# BackplaneConnector.net
KiCad netlist of a schematic drawn in Altium Designer
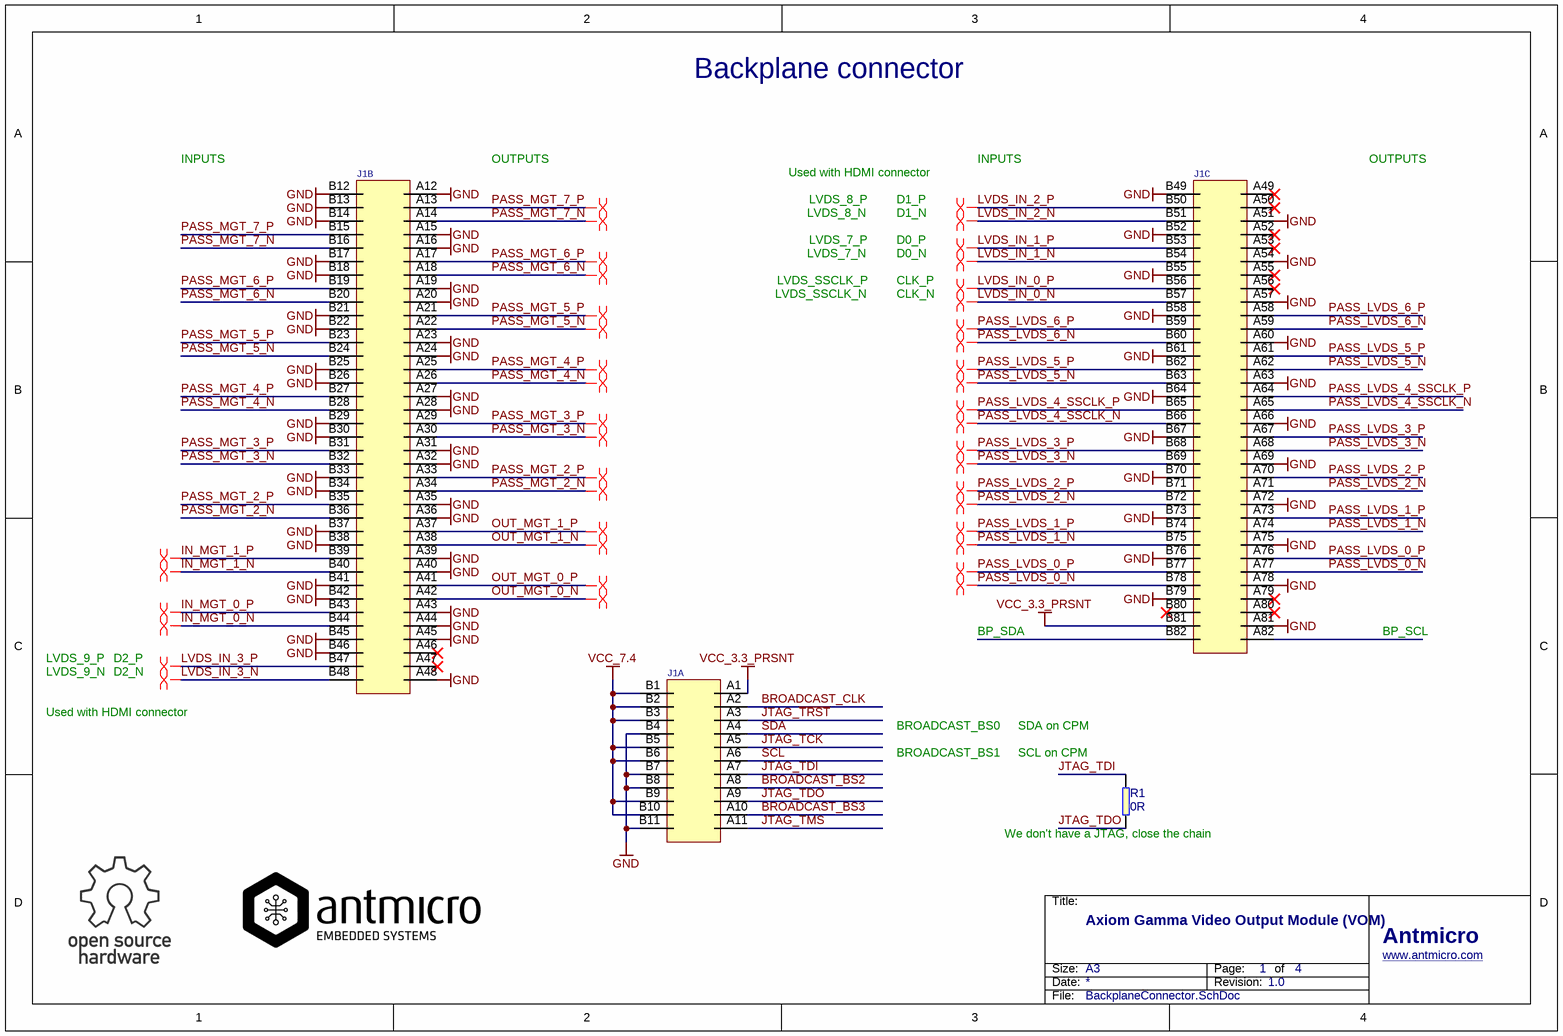
[diagram p0: BackplaneConnector.SchDoc]

(export (version "E")
  (design (tool "Eeschema 10.0.6"))
  (components
    (comp (ref "J1")
      (value "~")
      (footprint "PCIEX16")
      (description "PCB Only")
      (fields (field (name "PART NUMBER") "PCIEX16") (field (name "MANUFACTURER") "PCB ONLY"))
      (libsource (lib "VOM") (part "PCIEX16"))
    )
    (comp (ref "R1")
      (value "0R")
      (footprint "0402")
      (description "SMT Resistor 0402")
      (fields (field (name "PART NUMBER") "R_0R_0402") (field (name "MANUFACTURER") "MULTICOMP"))
      (libsource (lib "VOM") (part "R_0R_0402"))
    )
  )
  (nets
    (net (code "1") (name "/BROADCAST_BS2") (class "Default")
      (node (ref "J1") (pin "A8") (pinfunction "A8_A8") (pintype "passive"))
    )
    (net (code "2") (name "/BROADCAST_BS3") (class "Default")
      (node (ref "J1") (pin "A10") (pinfunction "A10_A10") (pintype "passive"))
    )
    (net (code "3") (name "/BROADCAST_CLK") (class "Default")
      (node (ref "J1") (pin "A2") (pinfunction "A2_A2") (pintype "passive"))
    )
    (net (code "4") (name "/IN_MGT_0_N") (class "Default")
      (node (ref "J1") (pin "B44") (pinfunction "B44_B44") (pintype "passive"))
    )
    (net (code "5") (name "/IN_MGT_0_P") (class "Default")
      (node (ref "J1") (pin "B43") (pinfunction "B43_B43") (pintype "passive"))
    )
    (net (code "6") (name "/IN_MGT_1_N") (class "Default")
      (node (ref "J1") (pin "B40") (pinfunction "B40_B40") (pintype "passive"))
    )
    (net (code "7") (name "/IN_MGT_1_P") (class "Default")
      (node (ref "J1") (pin "B39") (pinfunction "B39_B39") (pintype "passive"))
    )
    (net (code "8") (name "/JTAG_TCK") (class "Default")
      (node (ref "J1") (pin "A5") (pinfunction "A5_A5") (pintype "passive"))
    )
    (net (code "9") (name "/JTAG_TDI") (class "Default")
      (node (ref "J1") (pin "A7") (pinfunction "A7_A7") (pintype "passive"))
      (node (ref "R1") (pin "2") (pintype "passive"))
    )
    (net (code "10") (name "/JTAG_TDO") (class "Default")
      (node (ref "J1") (pin "A9") (pinfunction "A9_A9") (pintype "passive"))
      (node (ref "R1") (pin "1") (pintype "passive"))
    )
    (net (code "11") (name "/JTAG_TMS") (class "Default")
      (node (ref "J1") (pin "A11") (pinfunction "A11_A11") (pintype "passive"))
    )
    (net (code "12") (name "/JTAG_~{TRST}") (class "Default")
      (node (ref "J1") (pin "A3") (pinfunction "A3_A3") (pintype "passive"))
    )
    (net (code "13") (name "/LVDS_IN_0_N") (class "Default")
      (node (ref "J1") (pin "B57") (pinfunction "B57_B57") (pintype "passive"))
    )
    (net (code "14") (name "/LVDS_IN_0_P") (class "Default")
      (node (ref "J1") (pin "B56") (pinfunction "B56_B56") (pintype "passive"))
    )
    (net (code "15") (name "/LVDS_IN_1_N") (class "Default")
      (node (ref "J1") (pin "B54") (pinfunction "B54_B54") (pintype "passive"))
    )
    (net (code "16") (name "/LVDS_IN_1_P") (class "Default")
      (node (ref "J1") (pin "B53") (pinfunction "B53_B53") (pintype "passive"))
    )
    (net (code "17") (name "/LVDS_IN_2_N") (class "Default")
      (node (ref "J1") (pin "B51") (pinfunction "B51_B51") (pintype "passive"))
    )
    (net (code "18") (name "/LVDS_IN_2_P") (class "Default")
      (node (ref "J1") (pin "B50") (pinfunction "B50_B50") (pintype "passive"))
    )
    (net (code "19") (name "/LVDS_IN_3_N") (class "Default")
      (node (ref "J1") (pin "B48") (pinfunction "B48_B48") (pintype "passive"))
    )
    (net (code "20") (name "/LVDS_IN_3_P") (class "Default")
      (node (ref "J1") (pin "B47") (pinfunction "B47_B47") (pintype "passive"))
    )
    (net (code "21") (name "/OUT_MGT_0_N") (class "Default")
      (node (ref "J1") (pin "A42") (pinfunction "A42_A42") (pintype "passive"))
    )
    (net (code "22") (name "/OUT_MGT_0_P") (class "Default")
      (node (ref "J1") (pin "A41") (pinfunction "A41_A41") (pintype "passive"))
    )
    (net (code "23") (name "/OUT_MGT_1_N") (class "Default")
      (node (ref "J1") (pin "A38") (pinfunction "A38_A38") (pintype "passive"))
    )
    (net (code "24") (name "/OUT_MGT_1_P") (class "Default")
      (node (ref "J1") (pin "A37") (pinfunction "A37_A37") (pintype "passive"))
    )
    (net (code "25") (name "/PASS_LVDS_0_N") (class "Default")
      (node (ref "J1") (pin "A77") (pinfunction "A77_A77") (pintype "passive"))
      (node (ref "J1") (pin "B78") (pinfunction "B78_B78") (pintype "passive"))
    )
    (net (code "26") (name "/PASS_LVDS_0_P") (class "Default")
      (node (ref "J1") (pin "A76") (pinfunction "A76_A76") (pintype "passive"))
      (node (ref "J1") (pin "B77") (pinfunction "B77_B77") (pintype "passive"))
    )
    (net (code "27") (name "/PASS_LVDS_1_N") (class "Default")
      (node (ref "J1") (pin "A74") (pinfunction "A74_A74") (pintype "passive"))
      (node (ref "J1") (pin "B75") (pinfunction "B75_B75") (pintype "passive"))
    )
    (net (code "28") (name "/PASS_LVDS_1_P") (class "Default")
      (node (ref "J1") (pin "A73") (pinfunction "A73_A73") (pintype "passive"))
      (node (ref "J1") (pin "B74") (pinfunction "B74_B74") (pintype "passive"))
    )
    (net (code "29") (name "/PASS_LVDS_2_N") (class "Default")
      (node (ref "J1") (pin "A71") (pinfunction "A71_A71") (pintype "passive"))
      (node (ref "J1") (pin "B72") (pinfunction "B72_B72") (pintype "passive"))
    )
    (net (code "30") (name "/PASS_LVDS_2_P") (class "Default")
      (node (ref "J1") (pin "A70") (pinfunction "A70_A70") (pintype "passive"))
      (node (ref "J1") (pin "B71") (pinfunction "B71_B71") (pintype "passive"))
    )
    (net (code "31") (name "/PASS_LVDS_3_N") (class "Default")
      (node (ref "J1") (pin "A68") (pinfunction "A68_A68") (pintype "passive"))
      (node (ref "J1") (pin "B69") (pinfunction "B69_B69") (pintype "passive"))
    )
    (net (code "32") (name "/PASS_LVDS_3_P") (class "Default")
      (node (ref "J1") (pin "A67") (pinfunction "A67_A67") (pintype "passive"))
      (node (ref "J1") (pin "B68") (pinfunction "B68_B68") (pintype "passive"))
    )
    (net (code "33") (name "/PASS_LVDS_4_SSCLK_N") (class "Default")
      (node (ref "J1") (pin "A65") (pinfunction "A65_A65") (pintype "passive"))
      (node (ref "J1") (pin "B66") (pinfunction "B66_B66") (pintype "passive"))
    )
    (net (code "34") (name "/PASS_LVDS_4_SSCLK_P") (class "Default")
      (node (ref "J1") (pin "A64") (pinfunction "A64_A64") (pintype "passive"))
      (node (ref "J1") (pin "B65") (pinfunction "B65_B65") (pintype "passive"))
    )
    (net (code "35") (name "/PASS_LVDS_5_N") (class "Default")
      (node (ref "J1") (pin "A62") (pinfunction "A62_A62") (pintype "passive"))
      (node (ref "J1") (pin "B63") (pinfunction "B63_B63") (pintype "passive"))
    )
    (net (code "36") (name "/PASS_LVDS_5_P") (class "Default")
      (node (ref "J1") (pin "A61") (pinfunction "A61_A61") (pintype "passive"))
      (node (ref "J1") (pin "B62") (pinfunction "B62_B62") (pintype "passive"))
    )
    (net (code "37") (name "/PASS_LVDS_6_N") (class "Default")
      (node (ref "J1") (pin "A59") (pinfunction "A59_A59") (pintype "passive"))
      (node (ref "J1") (pin "B60") (pinfunction "B60_B60") (pintype "passive"))
    )
    (net (code "38") (name "/PASS_LVDS_6_P") (class "Default")
      (node (ref "J1") (pin "A58") (pinfunction "A58_A58") (pintype "passive"))
      (node (ref "J1") (pin "B59") (pinfunction "B59_B59") (pintype "passive"))
    )
    (net (code "39") (name "/PASS_MGT_2_N") (class "Default")
      (node (ref "J1") (pin "A34") (pinfunction "A34_A34") (pintype "passive"))
      (node (ref "J1") (pin "B36") (pinfunction "B36_B36") (pintype "passive"))
    )
    (net (code "40") (name "/PASS_MGT_2_P") (class "Default")
      (node (ref "J1") (pin "A33") (pinfunction "A33_A33") (pintype "passive"))
      (node (ref "J1") (pin "B35") (pinfunction "B35_B35") (pintype "passive"))
    )
    (net (code "41") (name "/PASS_MGT_3_N") (class "Default")
      (node (ref "J1") (pin "A30") (pinfunction "A30_A30") (pintype "passive"))
      (node (ref "J1") (pin "B32") (pinfunction "B32_B32") (pintype "passive"))
    )
    (net (code "42") (name "/PASS_MGT_3_P") (class "Default")
      (node (ref "J1") (pin "A29") (pinfunction "A29_A29") (pintype "passive"))
      (node (ref "J1") (pin "B31") (pinfunction "B31_B31") (pintype "passive"))
    )
    (net (code "43") (name "/PASS_MGT_4_N") (class "Default")
      (node (ref "J1") (pin "A26") (pinfunction "A26_A26") (pintype "passive"))
      (node (ref "J1") (pin "B28") (pinfunction "B28_B28") (pintype "passive"))
    )
    (net (code "44") (name "/PASS_MGT_4_P") (class "Default")
      (node (ref "J1") (pin "A25") (pinfunction "A25_A25") (pintype "passive"))
      (node (ref "J1") (pin "B27") (pinfunction "B27_B27") (pintype "passive"))
    )
    (net (code "45") (name "/PASS_MGT_5_N") (class "Default")
      (node (ref "J1") (pin "A22") (pinfunction "A22_A22") (pintype "passive"))
      (node (ref "J1") (pin "B24") (pinfunction "B24_B24") (pintype "passive"))
    )
    (net (code "46") (name "/PASS_MGT_5_P") (class "Default")
      (node (ref "J1") (pin "A21") (pinfunction "A21_A21") (pintype "passive"))
      (node (ref "J1") (pin "B23") (pinfunction "B23_B23") (pintype "passive"))
    )
    (net (code "47") (name "/PASS_MGT_6_N") (class "Default")
      (node (ref "J1") (pin "A18") (pinfunction "A18_A18") (pintype "passive"))
      (node (ref "J1") (pin "B20") (pinfunction "B20_B20") (pintype "passive"))
    )
    (net (code "48") (name "/PASS_MGT_6_P") (class "Default")
      (node (ref "J1") (pin "A17") (pinfunction "A17_A17") (pintype "passive"))
      (node (ref "J1") (pin "B19") (pinfunction "B19_B19") (pintype "passive"))
    )
    (net (code "49") (name "/PASS_MGT_7_N") (class "Default")
      (node (ref "J1") (pin "A14") (pinfunction "A14_A14") (pintype "passive"))
      (node (ref "J1") (pin "B16") (pinfunction "B16_B16") (pintype "passive"))
    )
    (net (code "50") (name "/PASS_MGT_7_P") (class "Default")
      (node (ref "J1") (pin "A13") (pinfunction "A13_A13") (pintype "passive"))
      (node (ref "J1") (pin "B15") (pinfunction "B15_B15") (pintype "passive"))
    )
    (net (code "51") (name "/SCL") (class "Default")
      (node (ref "J1") (pin "A6") (pinfunction "A6_A6") (pintype "passive"))
    )
    (net (code "52") (name "/SDA") (class "Default")
      (node (ref "J1") (pin "A4") (pinfunction "A4_A4") (pintype "passive"))
    )
    (net (code "53") (name "GND") (class "Default")
      (node (ref "J1") (pin "A12") (pinfunction "A12_A12") (pintype "passive"))
      (node (ref "J1") (pin "A15") (pinfunction "A15_A15") (pintype "passive"))
      (node (ref "J1") (pin "A16") (pinfunction "A16_A16") (pintype "passive"))
      (node (ref "J1") (pin "A19") (pinfunction "A19_A19") (pintype "passive"))
      (node (ref "J1") (pin "A20") (pinfunction "A20_A20") (pintype "passive"))
      (node (ref "J1") (pin "A23") (pinfunction "A23_A23") (pintype "passive"))
      (node (ref "J1") (pin "A24") (pinfunction "A24_A24") (pintype "passive"))
      (node (ref "J1") (pin "A27") (pinfunction "A27_A27") (pintype "passive"))
      (node (ref "J1") (pin "A28") (pinfunction "A28_A28") (pintype "passive"))
      (node (ref "J1") (pin "A31") (pinfunction "A31_A31") (pintype "passive"))
      (node (ref "J1") (pin "A32") (pinfunction "A32_A32") (pintype "passive"))
      (node (ref "J1") (pin "A35") (pinfunction "A35_A35") (pintype "passive"))
      (node (ref "J1") (pin "A36") (pinfunction "A36_A36") (pintype "passive"))
      (node (ref "J1") (pin "A39") (pinfunction "A39_A39") (pintype "passive"))
      (node (ref "J1") (pin "A40") (pinfunction "A40_A40") (pintype "passive"))
      (node (ref "J1") (pin "A43") (pinfunction "A43_A43") (pintype "passive"))
      (node (ref "J1") (pin "A44") (pinfunction "A44_A44") (pintype "passive"))
      (node (ref "J1") (pin "A45") (pinfunction "A45_A45") (pintype "passive"))
      (node (ref "J1") (pin "A48") (pinfunction "A48_A48") (pintype "passive"))
      (node (ref "J1") (pin "A51") (pinfunction "A51_A51") (pintype "passive"))
      (node (ref "J1") (pin "A54") (pinfunction "A54_A54") (pintype "passive"))
      (node (ref "J1") (pin "A57") (pinfunction "A57_A57") (pintype "passive"))
      (node (ref "J1") (pin "A60") (pinfunction "A60_A60") (pintype "passive"))
      (node (ref "J1") (pin "A63") (pinfunction "A63_A63") (pintype "passive"))
      (node (ref "J1") (pin "A66") (pinfunction "A66_A66") (pintype "passive"))
      (node (ref "J1") (pin "A69") (pinfunction "A69_A69") (pintype "passive"))
      (node (ref "J1") (pin "A72") (pinfunction "A72_A72") (pintype "passive"))
      (node (ref "J1") (pin "A75") (pinfunction "A75_A75") (pintype "passive"))
      (node (ref "J1") (pin "A78") (pinfunction "A78_A78") (pintype "passive"))
      (node (ref "J1") (pin "A81") (pinfunction "A81_A81") (pintype "passive"))
      (node (ref "J1") (pin "B11") (pinfunction "B11_B11") (pintype "passive"))
      (node (ref "J1") (pin "B12") (pinfunction "B12_B12") (pintype "passive"))
      (node (ref "J1") (pin "B13") (pinfunction "B13_B13") (pintype "passive"))
      (node (ref "J1") (pin "B14") (pinfunction "B14_B14") (pintype "passive"))
      (node (ref "J1") (pin "B17") (pinfunction "B17_B17") (pintype "passive"))
      (node (ref "J1") (pin "B18") (pinfunction "B18_B18") (pintype "passive"))
      (node (ref "J1") (pin "B21") (pinfunction "B21_B21") (pintype "passive"))
      (node (ref "J1") (pin "B22") (pinfunction "B22_B22") (pintype "passive"))
      (node (ref "J1") (pin "B25") (pinfunction "B25_B25") (pintype "passive"))
      (node (ref "J1") (pin "B26") (pinfunction "B26_B26") (pintype "passive"))
      (node (ref "J1") (pin "B29") (pinfunction "B29_B29") (pintype "passive"))
      (node (ref "J1") (pin "B30") (pinfunction "B30_B30") (pintype "passive"))
      (node (ref "J1") (pin "B33") (pinfunction "B33_B33") (pintype "passive"))
      (node (ref "J1") (pin "B34") (pinfunction "B34_B34") (pintype "passive"))
      (node (ref "J1") (pin "B37") (pinfunction "B37_B37") (pintype "passive"))
      (node (ref "J1") (pin "B38") (pinfunction "B38_B38") (pintype "passive"))
      (node (ref "J1") (pin "B4") (pinfunction "B4_B4") (pintype "passive"))
      (node (ref "J1") (pin "B41") (pinfunction "B41_B41") (pintype "passive"))
      (node (ref "J1") (pin "B42") (pinfunction "B42_B42") (pintype "passive"))
      (node (ref "J1") (pin "B45") (pinfunction "B45_B45") (pintype "passive"))
      (node (ref "J1") (pin "B46") (pinfunction "B46_B46") (pintype "passive"))
      (node (ref "J1") (pin "B49") (pinfunction "B49_B49") (pintype "passive"))
      (node (ref "J1") (pin "B52") (pinfunction "B52_B52") (pintype "passive"))
      (node (ref "J1") (pin "B55") (pinfunction "B55_B55") (pintype "passive"))
      (node (ref "J1") (pin "B58") (pinfunction "B58_B58") (pintype "passive"))
      (node (ref "J1") (pin "B61") (pinfunction "B61_B61") (pintype "passive"))
      (node (ref "J1") (pin "B64") (pinfunction "B64_B64") (pintype "passive"))
      (node (ref "J1") (pin "B67") (pinfunction "B67_B67") (pintype "passive"))
      (node (ref "J1") (pin "B7") (pinfunction "B7_B7") (pintype "passive"))
      (node (ref "J1") (pin "B70") (pinfunction "B70_B70") (pintype "passive"))
      (node (ref "J1") (pin "B73") (pinfunction "B73_B73") (pintype "passive"))
      (node (ref "J1") (pin "B76") (pinfunction "B76_B76") (pintype "passive"))
      (node (ref "J1") (pin "B79") (pinfunction "B79_B79") (pintype "passive"))
      (node (ref "J1") (pin "B8") (pinfunction "B8_B8") (pintype "passive"))
    )
    (net (code "54") (name "VCC_3.3_PRSNT") (class "Default")
      (node (ref "J1") (pin "A1") (pinfunction "A1_A1") (pintype "passive"))
      (node (ref "J1") (pin "B81") (pinfunction "B81_B81") (pintype "passive"))
    )
    (net (code "55") (name "VCC_7.4") (class "Default")
      (node (ref "J1") (pin "B1") (pinfunction "B1_B1") (pintype "passive"))
      (node (ref "J1") (pin "B10") (pinfunction "B10_B10") (pintype "passive"))
      (node (ref "J1") (pin "B2") (pinfunction "B2_B2") (pintype "passive"))
      (node (ref "J1") (pin "B3") (pinfunction "B3_B3") (pintype "passive"))
      (node (ref "J1") (pin "B5") (pinfunction "B5_B5") (pintype "passive"))
      (node (ref "J1") (pin "B6") (pinfunction "B6_B6") (pintype "passive"))
      (node (ref "J1") (pin "B9") (pinfunction "B9_B9") (pintype "passive"))
    )
    (net (code "56") (name "unconnected-(J1-PadA46)") (class "Default")
      (node (ref "J1") (pin "A46") (pinfunction "A46_A46") (pintype "passive+no_connect"))
    )
    (net (code "57") (name "unconnected-(J1-PadA47)") (class "Default")
      (node (ref "J1") (pin "A47") (pinfunction "A47_A47") (pintype "passive+no_connect"))
    )
    (net (code "58") (name "unconnected-(J1-PadA49)") (class "Default")
      (node (ref "J1") (pin "A49") (pinfunction "A49_A49") (pintype "passive+no_connect"))
    )
    (net (code "59") (name "unconnected-(J1-PadA50)") (class "Default")
      (node (ref "J1") (pin "A50") (pinfunction "A50_A50") (pintype "passive+no_connect"))
    )
    (net (code "60") (name "unconnected-(J1-PadA52)") (class "Default")
      (node (ref "J1") (pin "A52") (pinfunction "A52_A52") (pintype "passive+no_connect"))
    )
    (net (code "61") (name "unconnected-(J1-PadA53)") (class "Default")
      (node (ref "J1") (pin "A53") (pinfunction "A53_A53") (pintype "passive+no_connect"))
    )
    (net (code "62") (name "unconnected-(J1-PadA55)") (class "Default")
      (node (ref "J1") (pin "A55") (pinfunction "A55_A55") (pintype "passive+no_connect"))
    )
    (net (code "63") (name "unconnected-(J1-PadA56)") (class "Default")
      (node (ref "J1") (pin "A56") (pinfunction "A56_A56") (pintype "passive+no_connect"))
    )
    (net (code "64") (name "unconnected-(J1-PadA79)") (class "Default")
      (node (ref "J1") (pin "A79") (pinfunction "A79_A79") (pintype "passive+no_connect"))
    )
    (net (code "65") (name "unconnected-(J1-PadA80)") (class "Default")
      (node (ref "J1") (pin "A80") (pinfunction "A80_A80") (pintype "passive+no_connect"))
    )
    (net (code "66") (name "unconnected-(J1-PadA82)") (class "Default")
      (node (ref "J1") (pin "A82") (pinfunction "A82_A82") (pintype "passive"))
    )
    (net (code "67") (name "unconnected-(J1-PadB80)") (class "Default")
      (node (ref "J1") (pin "B80") (pinfunction "B80_B80") (pintype "passive+no_connect"))
    )
    (net (code "68") (name "unconnected-(J1-PadB82)") (class "Default")
      (node (ref "J1") (pin "B82") (pinfunction "B82_B82") (pintype "passive"))
    )
  )
)
